# Interconnect_Board.net
KiCad netlist of a schematic drawn in EasyEDA Pro
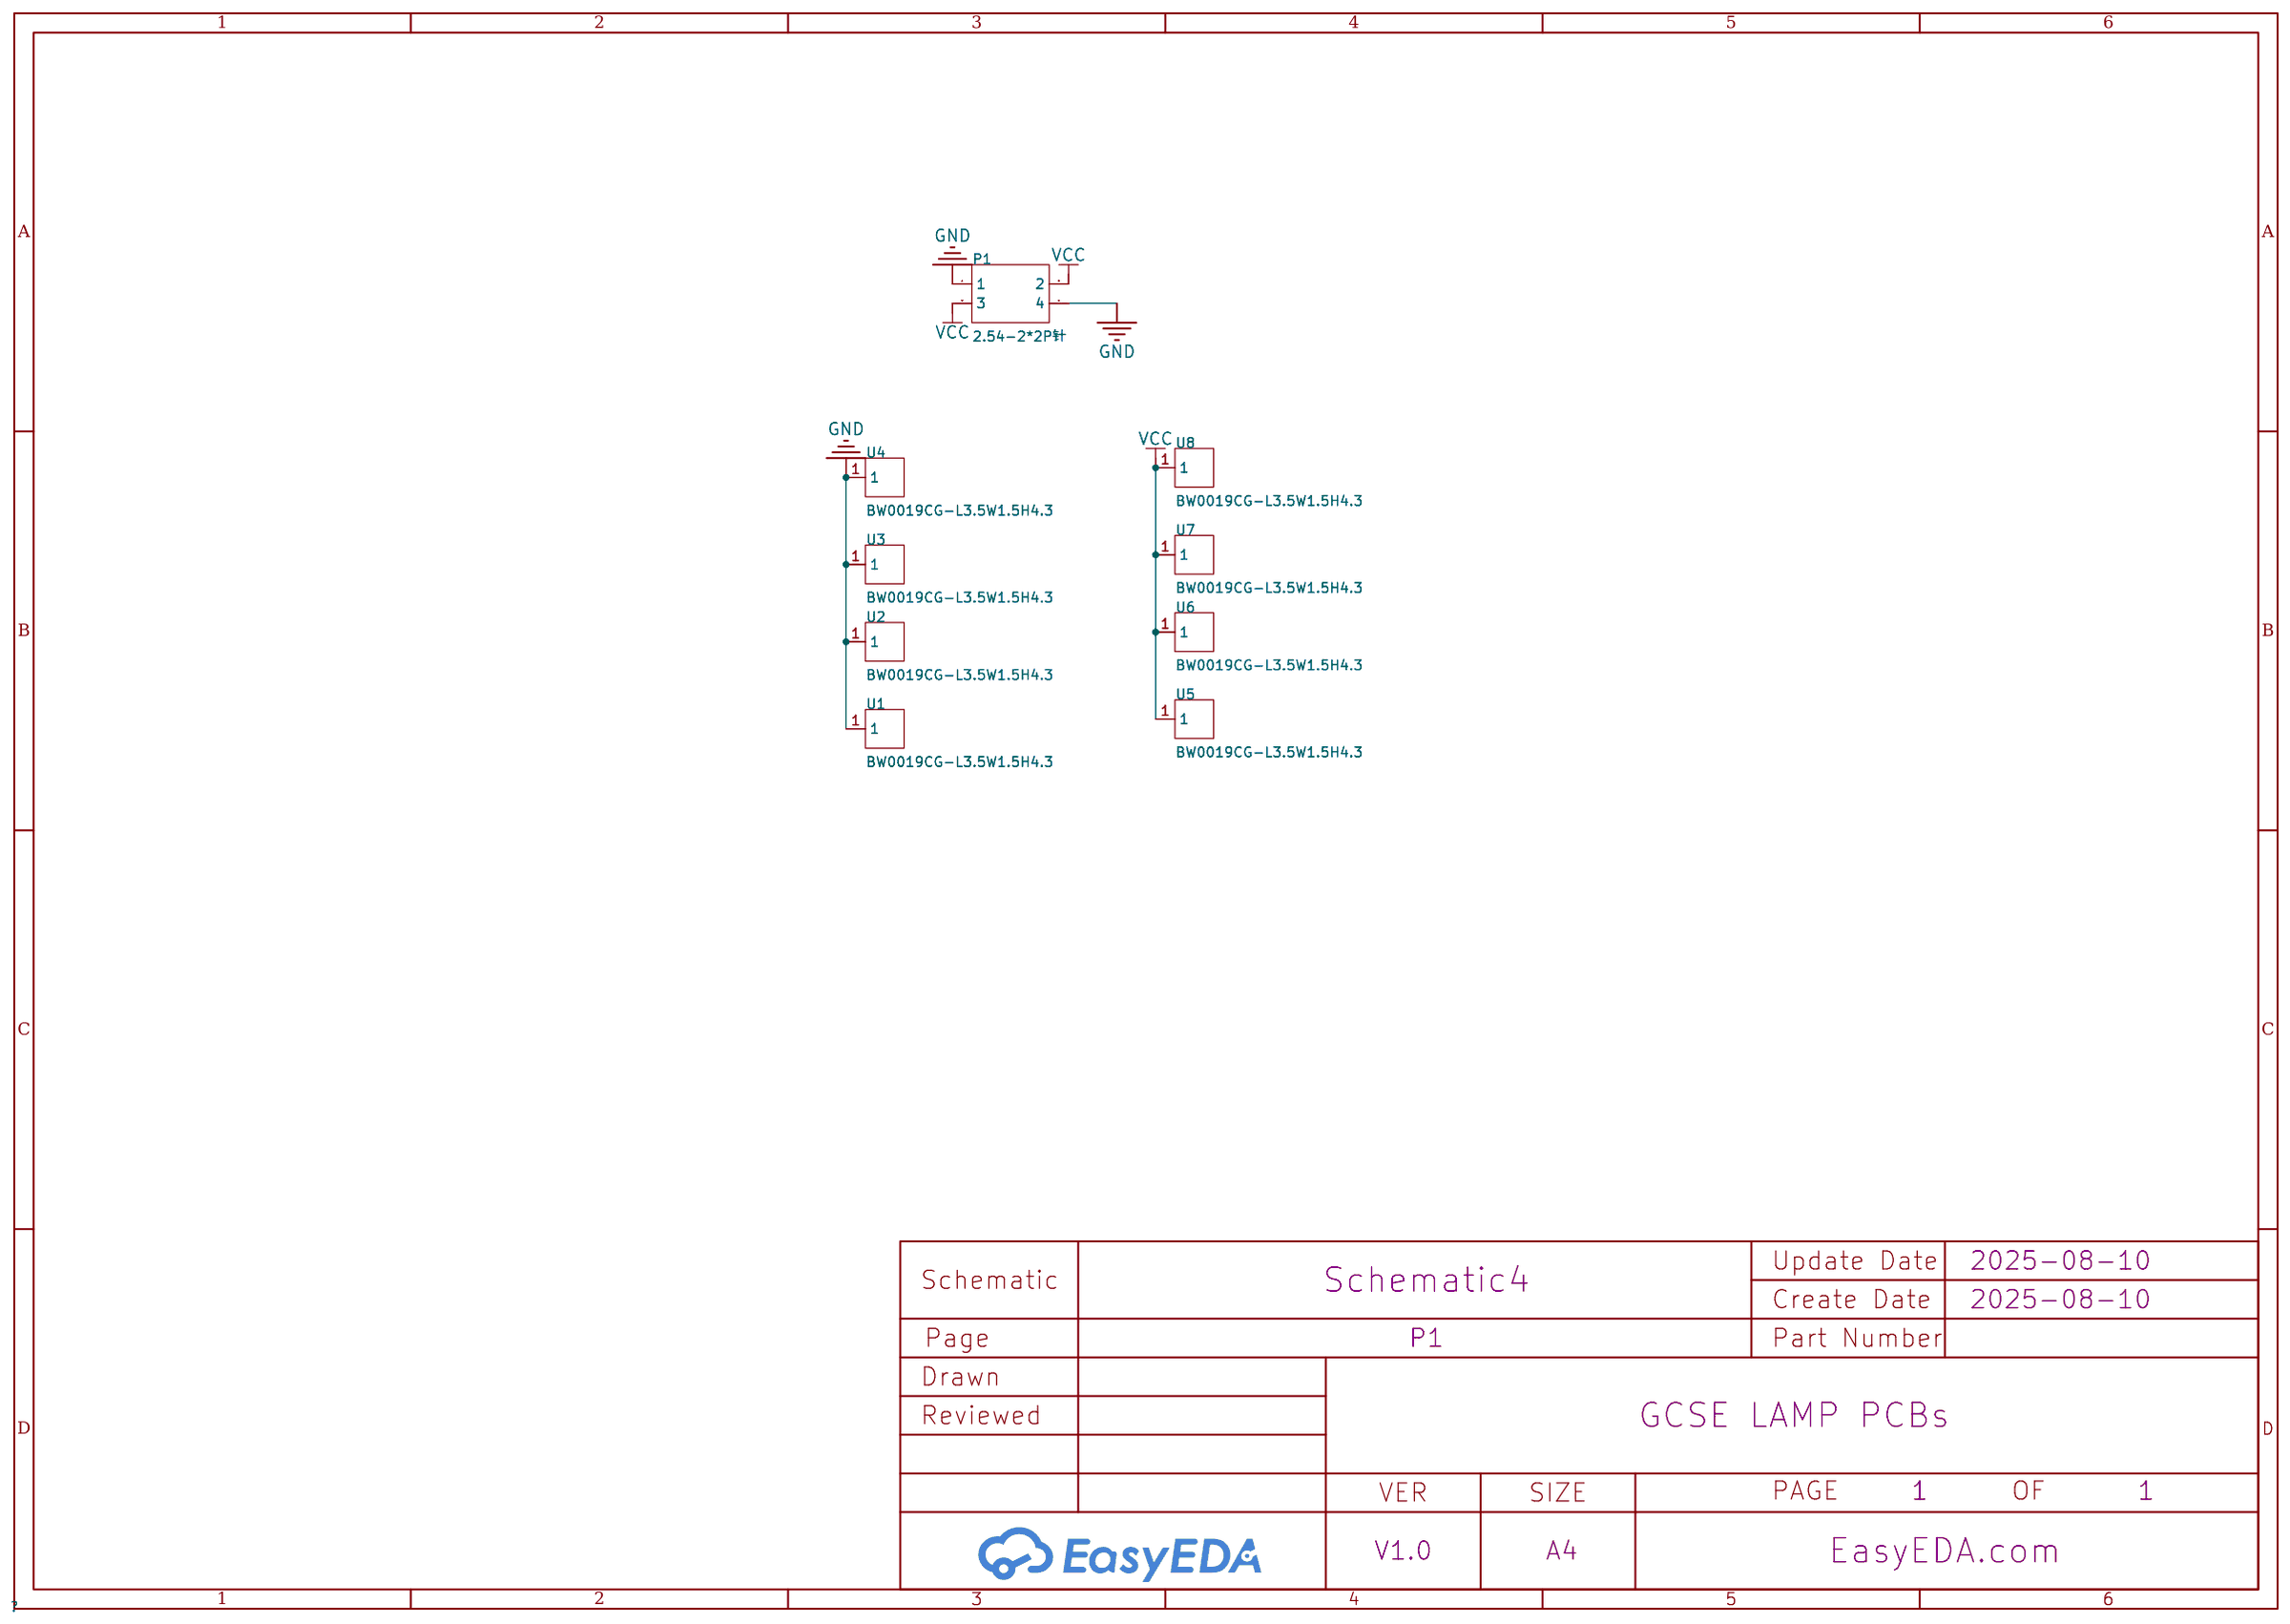
[diagram p0: schematic sheet]

(export (version "E")
  (design (tool "Eeschema 10.0.6"))
  (components
    (comp (ref "P1")
      (value "2.54-2*2P针")
      (footprint "easyedapro:HDR-TH_4P-P2.54-V-M-R2-C2-S2.54-1")
      (fields (field (name "Manufacturer") "BOOMELE(博穆精密)"))
      (libsource (lib "easyedapro") (part "Header-Male-2.54_2x2"))
    )
    (comp (ref "U1")
      (value "BW0019CG-L3.5W1.5H4.3")
      (footprint "easyedapro:ANT-SMD_L3.5-W1.5")
      (fields (field (name "Manufacturer") "BAT WIRELESS(蝙蝠无线)"))
      (libsource (lib "easyedapro") (part "BW0019CG-L3.5W1.5H4.3"))
    )
    (comp (ref "U2")
      (value "BW0019CG-L3.5W1.5H4.3")
      (footprint "easyedapro:ANT-SMD_L3.5-W1.5")
      (fields (field (name "Manufacturer") "BAT WIRELESS(蝙蝠无线)"))
      (libsource (lib "easyedapro") (part "BW0019CG-L3.5W1.5H4.3"))
    )
    (comp (ref "U3")
      (value "BW0019CG-L3.5W1.5H4.3")
      (footprint "easyedapro:ANT-SMD_L3.5-W1.5")
      (fields (field (name "Manufacturer") "BAT WIRELESS(蝙蝠无线)"))
      (libsource (lib "easyedapro") (part "BW0019CG-L3.5W1.5H4.3"))
    )
    (comp (ref "U4")
      (value "BW0019CG-L3.5W1.5H4.3")
      (footprint "easyedapro:ANT-SMD_L3.5-W1.5")
      (fields (field (name "Manufacturer") "BAT WIRELESS(蝙蝠无线)"))
      (libsource (lib "easyedapro") (part "BW0019CG-L3.5W1.5H4.3"))
    )
    (comp (ref "U5")
      (value "BW0019CG-L3.5W1.5H4.3")
      (footprint "easyedapro:ANT-SMD_L3.5-W1.5")
      (fields (field (name "Manufacturer") "BAT WIRELESS(蝙蝠无线)"))
      (libsource (lib "easyedapro") (part "BW0019CG-L3.5W1.5H4.3"))
    )
    (comp (ref "U6")
      (value "BW0019CG-L3.5W1.5H4.3")
      (footprint "easyedapro:ANT-SMD_L3.5-W1.5")
      (fields (field (name "Manufacturer") "BAT WIRELESS(蝙蝠无线)"))
      (libsource (lib "easyedapro") (part "BW0019CG-L3.5W1.5H4.3"))
    )
    (comp (ref "U7")
      (value "BW0019CG-L3.5W1.5H4.3")
      (footprint "easyedapro:ANT-SMD_L3.5-W1.5")
      (fields (field (name "Manufacturer") "BAT WIRELESS(蝙蝠无线)"))
      (libsource (lib "easyedapro") (part "BW0019CG-L3.5W1.5H4.3"))
    )
    (comp (ref "U8")
      (value "BW0019CG-L3.5W1.5H4.3")
      (footprint "easyedapro:ANT-SMD_L3.5-W1.5")
      (fields (field (name "Manufacturer") "BAT WIRELESS(蝙蝠无线)"))
      (libsource (lib "easyedapro") (part "BW0019CG-L3.5W1.5H4.3"))
    )
  )
  (nets
    (net (code "1") (name "GND") (class "Default")
      (node (ref "P1") (pin "1") (pinfunction "1_1") (pintype "input"))
      (node (ref "P1") (pin "4") (pinfunction "4_4") (pintype "input"))
      (node (ref "U1") (pin "1") (pinfunction "1_1") (pintype "unspecified"))
      (node (ref "U2") (pin "1") (pinfunction "1_1") (pintype "unspecified"))
      (node (ref "U3") (pin "1") (pinfunction "1_1") (pintype "unspecified"))
      (node (ref "U4") (pin "1") (pinfunction "1_1") (pintype "unspecified"))
    )
    (net (code "2") (name "VCC") (class "Default")
      (node (ref "P1") (pin "2") (pinfunction "2_2") (pintype "input"))
      (node (ref "P1") (pin "3") (pinfunction "3_3") (pintype "input"))
      (node (ref "U5") (pin "1") (pinfunction "1_1") (pintype "unspecified"))
      (node (ref "U6") (pin "1") (pinfunction "1_1") (pintype "unspecified"))
      (node (ref "U7") (pin "1") (pinfunction "1_1") (pintype "unspecified"))
      (node (ref "U8") (pin "1") (pinfunction "1_1") (pintype "unspecified"))
    )
  )
)
